# 19V_Converter3_12_2018.net
KiCad netlist of a schematic drawn in Altium Designer
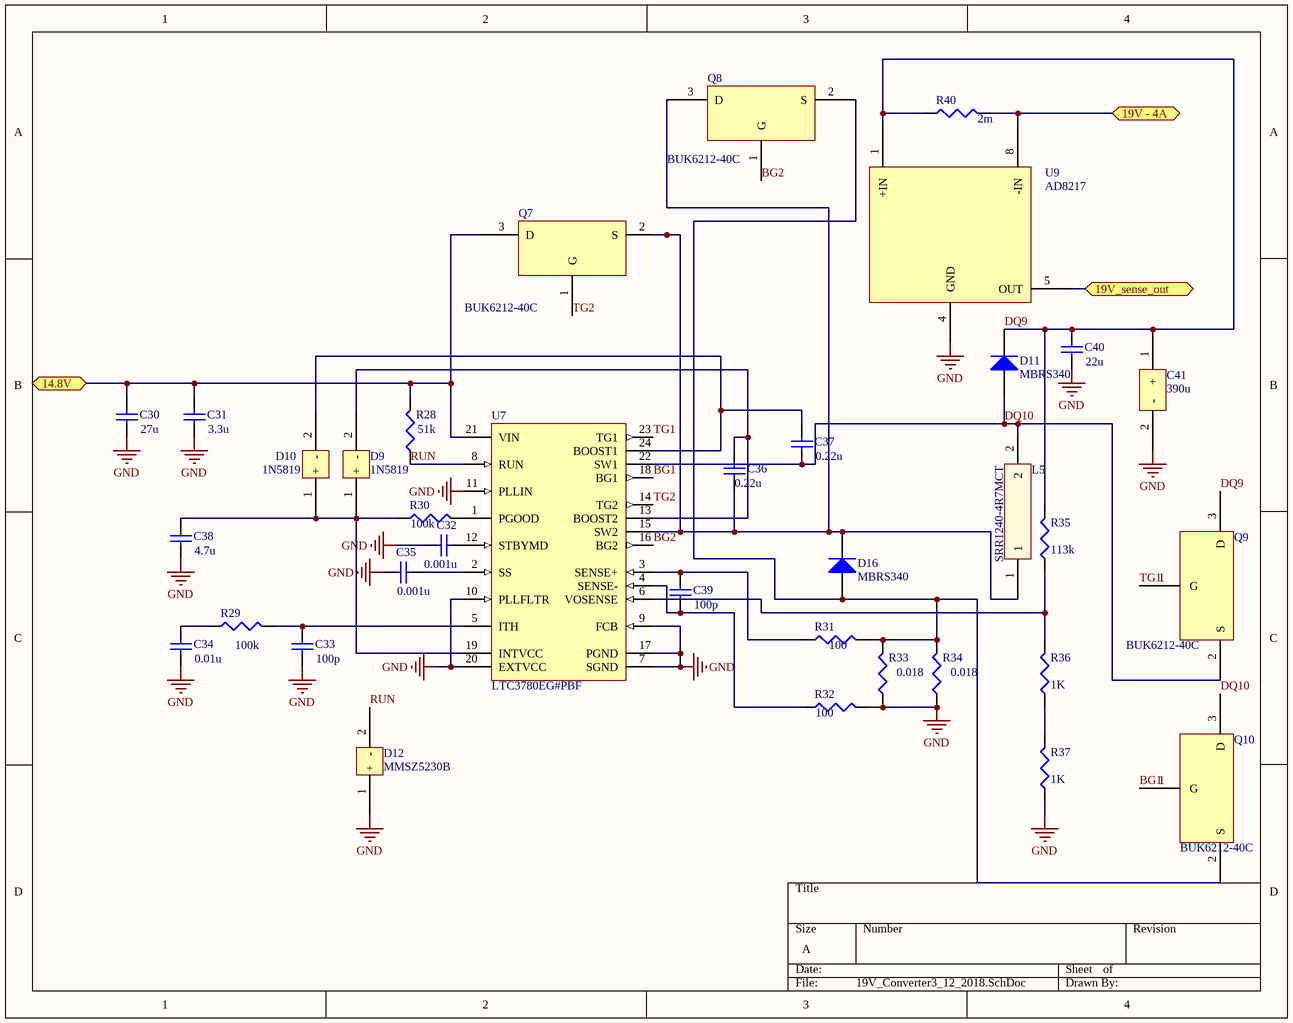
[diagram p0: 19V_Converter3_12_2018.SchDoc]

(export (version "E")
  (design (tool "Eeschema 10.0.6"))
  (components
    (comp (ref "C30")
      (value "27u")
      (footprint "C1206")
      (description "Capacitor (Semiconductor SIM Model)")
      (fields (field (name "Comment") "Cap Semi") (field (name "PUBLISHER") "Altium Limited"))
      (libsource (lib "Miscellaneous Devices") (part "Cap Semi"))
    )
    (comp (ref "C31")
      (value "3.3u")
      (footprint "C1206")
      (description "Capacitor (Semiconductor SIM Model)")
      (fields (field (name "Comment") "Cap Semi") (field (name "PUBLISHER") "Altium Limited"))
      (libsource (lib "Miscellaneous Devices") (part "Cap Semi"))
    )
    (comp (ref "C32")
      (value "0.001u")
      (footprint "C1206")
      (description "Capacitor (Semiconductor SIM Model)")
      (fields (field (name "Comment") "Cap Semi") (field (name "PUBLISHER") "Altium Limited"))
      (libsource (lib "Miscellaneous Devices") (part "Cap Semi"))
    )
    (comp (ref "C33")
      (value "100p")
      (footprint "C1206")
      (description "Capacitor (Semiconductor SIM Model)")
      (fields (field (name "Comment") "Cap Semi") (field (name "PUBLISHER") "Altium Limited"))
      (libsource (lib "Miscellaneous Devices") (part "Cap Semi"))
    )
    (comp (ref "C34")
      (value "0.01u")
      (footprint "C1206")
      (description "Capacitor (Semiconductor SIM Model)")
      (fields (field (name "Comment") "Cap Semi") (field (name "PUBLISHER") "Altium Limited"))
      (libsource (lib "Miscellaneous Devices") (part "Cap Semi"))
    )
    (comp (ref "C35")
      (value "0.001u")
      (footprint "C1206")
      (description "Capacitor (Semiconductor SIM Model)")
      (fields (field (name "Comment") "Cap Semi") (field (name "PUBLISHER") "Altium Limited"))
      (libsource (lib "Miscellaneous Devices") (part "Cap Semi"))
    )
    (comp (ref "C36")
      (value "0.22u")
      (footprint "C1206")
      (description "Capacitor (Semiconductor SIM Model)")
      (fields (field (name "Comment") "Cap Semi") (field (name "PUBLISHER") "Altium Limited"))
      (libsource (lib "Miscellaneous Devices") (part "Cap Semi"))
    )
    (comp (ref "C37")
      (value "0.22u")
      (footprint "C1206")
      (description "Capacitor (Semiconductor SIM Model)")
      (fields (field (name "Comment") "Cap Semi") (field (name "PUBLISHER") "Altium Limited"))
      (libsource (lib "Miscellaneous Devices") (part "Cap Semi"))
    )
    (comp (ref "C38")
      (value "4.7u")
      (footprint "C1206")
      (description "Capacitor (Semiconductor SIM Model)")
      (fields (field (name "Comment") "Cap Semi") (field (name "PUBLISHER") "Altium Limited"))
      (libsource (lib "Miscellaneous Devices") (part "Cap Semi"))
    )
    (comp (ref "C39")
      (value "100p")
      (footprint "C1206")
      (description "Capacitor (Semiconductor SIM Model)")
      (fields (field (name "Comment") "Cap Semi") (field (name "PUBLISHER") "Altium Limited"))
      (libsource (lib "Miscellaneous Devices") (part "Cap Semi"))
    )
    (comp (ref "C40")
      (value "22u")
      (footprint "C1206")
      (description "Capacitor (Semiconductor SIM Model)")
      (fields (field (name "Comment") "Cap Semi") (field (name "PUBLISHER") "Altium Limited"))
      (libsource (lib "Miscellaneous Devices") (part "Cap Semi"))
    )
    (comp (ref "C41")
      (value "390u")
      (footprint "CAPR5-4X5")
      (libsource (lib "AluminumCap") (part "Alum_Cap"))
    )
    (comp (ref "D9")
      (value "1N5819")
      (footprint "SODFL370X175-2N")
      (libsource (lib "Diode (1N5819)") (part "Component_1"))
    )
    (comp (ref "D10")
      (value "1N5819")
      (footprint "SODFL370X175-2N")
      (libsource (lib "Diode (1N5819)") (part "Component_1"))
    )
    (comp (ref "D11")
      (value "MBRS340")
      (footprint "SMC")
      (description "Default Diode")
      (fields (field (name "PUBLISHER") "Altium Limited"))
      (libsource (lib "Miscellaneous Devices") (part "Diode"))
    )
    (comp (ref "D12")
      (value "MMSZ5230B")
      (footprint "SODFL370X175-2N")
      (libsource (lib "Diode (1N5819)") (part "Component_1"))
    )
    (comp (ref "D16")
      (value "MBRS340")
      (footprint "SMC")
      (description "Default Diode")
      (fields (field (name "PUBLISHER") "Altium Limited"))
      (libsource (lib "Miscellaneous Devices") (part "Diode"))
    )
    (comp (ref "L5")
      (value "SRR1240-4R7MCT")
      (footprint "INDP125125X40N")
      (libsource (lib "SRR1240-4R7MCT") (part "SRR1240-4R7MCT"))
    )
    (comp (ref "Q7")
      (value "BUK6212-40C")
      (footprint "DPAK228P1000X238-3N")
      (libsource (lib "BUK6212-40C") (part "Component_1"))
    )
    (comp (ref "Q8")
      (value "BUK6212-40C")
      (footprint "DPAK228P1000X238-3N")
      (libsource (lib "BUK6212-40C") (part "Component_1"))
    )
    (comp (ref "Q9")
      (value "BUK6212-40C")
      (footprint "DPAK228P1000X238-3N")
      (libsource (lib "") (part "Component_1_1"))
    )
    (comp (ref "Q10")
      (value "BUK6212-40C")
      (footprint "DPAK228P1000X238-3N")
      (libsource (lib "") (part "Component_1_1"))
    )
    (comp (ref "R28")
      (value "51k")
      (footprint "J1-0603")
      (description "Resistor")
      (fields (field (name "Comment") "Res3") (field (name "PUBLISHER") "Altium Limited"))
      (libsource (lib "Miscellaneous Devices") (part "Res3"))
    )
    (comp (ref "R29")
      (value "100k")
      (footprint "J1-0603")
      (description "Resistor")
      (fields (field (name "Comment") "Res3") (field (name "PUBLISHER") "Altium Limited"))
      (libsource (lib "Miscellaneous Devices") (part "Res3"))
    )
    (comp (ref "R30")
      (value "100k")
      (footprint "J1-0603")
      (description "Resistor")
      (fields (field (name "Comment") "Res3") (field (name "PUBLISHER") "Altium Limited"))
      (libsource (lib "Miscellaneous Devices") (part "Res3"))
    )
    (comp (ref "R31")
      (value "100")
      (footprint "J1-0603")
      (description "Resistor")
      (fields (field (name "Comment") "Res3") (field (name "PUBLISHER") "Altium Limited"))
      (libsource (lib "Miscellaneous Devices") (part "Res3"))
    )
    (comp (ref "R32")
      (value "100")
      (footprint "J1-0603")
      (description "Resistor")
      (fields (field (name "Comment") "Res3") (field (name "PUBLISHER") "Altium Limited"))
      (libsource (lib "Miscellaneous Devices") (part "Res3"))
    )
    (comp (ref "R33")
      (value "0.018")
      (footprint "J1-0603")
      (description "Resistor")
      (fields (field (name "Comment") "Res3") (field (name "PUBLISHER") "Altium Limited"))
      (libsource (lib "Miscellaneous Devices") (part "Res3"))
    )
    (comp (ref "R34")
      (value "0.018")
      (footprint "J1-0603")
      (description "Resistor")
      (fields (field (name "Comment") "Res3") (field (name "PUBLISHER") "Altium Limited"))
      (libsource (lib "Miscellaneous Devices") (part "Res3"))
    )
    (comp (ref "R35")
      (value "113k")
      (footprint "J1-0603")
      (description "Resistor")
      (fields (field (name "Comment") "Res3") (field (name "PUBLISHER") "Altium Limited"))
      (libsource (lib "Miscellaneous Devices") (part "Res3"))
    )
    (comp (ref "R36")
      (value "1K")
      (footprint "J1-0603")
      (description "Resistor")
      (fields (field (name "Comment") "Res3") (field (name "PUBLISHER") "Altium Limited"))
      (libsource (lib "Miscellaneous Devices") (part "Res3"))
    )
    (comp (ref "R37")
      (value "1K")
      (footprint "J1-0603")
      (description "Resistor")
      (fields (field (name "Comment") "Res3") (field (name "PUBLISHER") "Altium Limited"))
      (libsource (lib "Miscellaneous Devices") (part "Res3"))
    )
    (comp (ref "R40")
      (value "2m")
      (footprint "14-1210")
      (description "Resistor")
      (fields (field (name "Comment") "Res3") (field (name "PUBLISHER") "Altium Limited"))
      (libsource (lib "Miscellaneous Devices") (part "Res3"))
    )
    (comp (ref "U7")
      (value "LTC3780EG#PBF")
      (footprint "SOP65P780X200-24N")
      (fields (field (name "MANUFACTURER") "Linear Technology"))
      (libsource (lib "Linear Technology Power Management Switching Regulator LTC1174-LTC3901") (part "LTC3780EG#PBF"))
    )
    (comp (ref "U9")
      (value "AD8217")
      (footprint "TSOP65P490X110-8N")
      (description "Current Shunt Moniter")
      (libsource (lib "AD8217") (part "Component_1"))
    )
  )
  (nets
    (net (code "1") (name "/14.8V") (class "Default")
      (node (ref "C30") (pin "2") (pinfunction "2_2") (pintype "passive"))
      (node (ref "C31") (pin "2") (pinfunction "2_2") (pintype "passive"))
      (node (ref "Q7") (pin "3") (pinfunction "D_3") (pintype "passive"))
      (node (ref "R28") (pin "2") (pinfunction "2_2") (pintype "passive"))
      (node (ref "U7") (pin "21") (pinfunction "VIN_21") (pintype "power_in"))
    )
    (net (code "2") (name "/19V - 4A") (class "Default")
      (node (ref "R40") (pin "2") (pinfunction "2_2") (pintype "passive"))
      (node (ref "U9") (pin "8") (pinfunction "-IN_8") (pintype "passive"))
    )
    (net (code "3") (name "/19V_sense_out") (class "Default")
      (node (ref "U9") (pin "5") (pinfunction "OUT_5") (pintype "passive"))
    )
    (net (code "4") (name "/BG1") (class "Default")
      (node (ref "Q10") (pin "1") (pinfunction "G_1") (pintype "passive"))
      (node (ref "U7") (pin "18") (pinfunction "BG1_18") (pintype "output"))
    )
    (net (code "5") (name "/BG2") (class "Default")
      (node (ref "Q8") (pin "1") (pinfunction "G_1") (pintype "passive"))
      (node (ref "U7") (pin "16") (pinfunction "BG2_16") (pintype "output"))
    )
    (net (code "6") (name "/DQ9") (class "Default")
      (node (ref "C40") (pin "2") (pinfunction "2_2") (pintype "passive"))
      (node (ref "C41") (pin "1") (pinfunction "+_1") (pintype "passive"))
      (node (ref "D11") (pin "2") (pinfunction "K_2") (pintype "passive"))
      (node (ref "Q9") (pin "3") (pinfunction "D_3") (pintype "passive"))
      (node (ref "R35") (pin "2") (pinfunction "2_2") (pintype "passive"))
      (node (ref "R40") (pin "1") (pinfunction "1_1") (pintype "passive"))
      (node (ref "U9") (pin "1") (pinfunction "+IN_1") (pintype "passive"))
    )
    (net (code "7") (name "/DQ10") (class "Default")
      (node (ref "C37") (pin "1") (pinfunction "1_1") (pintype "passive"))
      (node (ref "D11") (pin "1") (pinfunction "A_1") (pintype "passive"))
      (node (ref "L5") (pin "2") (pinfunction "2_2") (pintype "passive"))
      (node (ref "Q10") (pin "3") (pinfunction "D_3") (pintype "passive"))
      (node (ref "Q9") (pin "2") (pinfunction "S_2") (pintype "passive"))
      (node (ref "U7") (pin "22") (pinfunction "SW1_22") (pintype "passive"))
    )
    (net (code "8") (name "/RUN") (class "Default")
      (node (ref "D12") (pin "2") (pinfunction "-_2") (pintype "passive"))
      (node (ref "R28") (pin "1") (pinfunction "1_1") (pintype "passive"))
      (node (ref "U7") (pin "8") (pinfunction "RUN_8") (pintype "input"))
    )
    (net (code "9") (name "/TG1") (class "Default")
      (node (ref "Q9") (pin "1") (pinfunction "G_1") (pintype "passive"))
      (node (ref "U7") (pin "23") (pinfunction "TG1_23") (pintype "output"))
    )
    (net (code "10") (name "/TG2") (class "Default")
      (node (ref "Q7") (pin "1") (pinfunction "G_1") (pintype "passive"))
      (node (ref "U7") (pin "14") (pinfunction "TG2_14") (pintype "output"))
    )
    (net (code "11") (name "GND") (class "Default")
      (node (ref "C30") (pin "1") (pinfunction "1_1") (pintype "passive"))
      (node (ref "C31") (pin "1") (pinfunction "1_1") (pintype "passive"))
      (node (ref "C32") (pin "1") (pinfunction "1_1") (pintype "passive"))
      (node (ref "C33") (pin "1") (pinfunction "1_1") (pintype "passive"))
      (node (ref "C34") (pin "1") (pinfunction "1_1") (pintype "passive"))
      (node (ref "C35") (pin "1") (pinfunction "1_1") (pintype "passive"))
      (node (ref "C38") (pin "1") (pinfunction "1_1") (pintype "passive"))
      (node (ref "C40") (pin "1") (pinfunction "1_1") (pintype "passive"))
      (node (ref "C41") (pin "2") (pinfunction "-_2") (pintype "passive"))
      (node (ref "D12") (pin "1") (pinfunction "+_1") (pintype "passive"))
      (node (ref "R32") (pin "2") (pinfunction "2_2") (pintype "passive"))
      (node (ref "R33") (pin "1") (pinfunction "1_1") (pintype "passive"))
      (node (ref "R34") (pin "1") (pinfunction "1_1") (pintype "passive"))
      (node (ref "R37") (pin "1") (pinfunction "1_1") (pintype "passive"))
      (node (ref "U7") (pin "10") (pinfunction "PLLFLTR_10") (pintype "input"))
      (node (ref "U7") (pin "11") (pinfunction "PLLIN_11") (pintype "input"))
      (node (ref "U7") (pin "17") (pinfunction "PGND_17") (pintype "power_in"))
      (node (ref "U7") (pin "20") (pinfunction "EXTVCC_20") (pintype "power_in"))
      (node (ref "U7") (pin "7") (pinfunction "SGND_7") (pintype "power_in"))
      (node (ref "U7") (pin "9") (pinfunction "FCB_9") (pintype "input"))
      (node (ref "U9") (pin "4") (pinfunction "GND_4") (pintype "passive"))
    )
    (net (code "12") (name "Net-(C34-Pad2)") (class "Default")
      (node (ref "C34") (pin "2") (pinfunction "2_2") (pintype "passive"))
      (node (ref "R29") (pin "1") (pinfunction "1_1") (pintype "passive"))
    )
    (net (code "13") (name "Net-(D9--)") (class "Default")
      (node (ref "C36") (pin "2") (pinfunction "2_2") (pintype "passive"))
      (node (ref "D9") (pin "2") (pinfunction "-_2") (pintype "passive"))
      (node (ref "U7") (pin "13") (pinfunction "BOOST2_13") (pintype "passive"))
    )
    (net (code "14") (name "Net-(D10-+)") (class "Default")
      (node (ref "C38") (pin "2") (pinfunction "2_2") (pintype "passive"))
      (node (ref "D10") (pin "1") (pinfunction "+_1") (pintype "passive"))
      (node (ref "D9") (pin "1") (pinfunction "+_1") (pintype "passive"))
      (node (ref "R30") (pin "1") (pinfunction "1_1") (pintype "passive"))
      (node (ref "U7") (pin "19") (pinfunction "INTVCC_19") (pintype "power_in"))
    )
    (net (code "15") (name "Net-(D10--)") (class "Default")
      (node (ref "C37") (pin "2") (pinfunction "2_2") (pintype "passive"))
      (node (ref "D10") (pin "2") (pinfunction "-_2") (pintype "passive"))
      (node (ref "U7") (pin "24") (pinfunction "BOOST1_24") (pintype "passive"))
    )
    (net (code "16") (name "Net-(D16-A)") (class "Default")
      (node (ref "D16") (pin "1") (pinfunction "A_1") (pintype "passive"))
      (node (ref "Q10") (pin "2") (pinfunction "S_2") (pintype "passive"))
      (node (ref "Q8") (pin "2") (pinfunction "S_2") (pintype "passive"))
      (node (ref "R31") (pin "2") (pinfunction "2_2") (pintype "passive"))
      (node (ref "R33") (pin "2") (pinfunction "2_2") (pintype "passive"))
      (node (ref "R34") (pin "2") (pinfunction "2_2") (pintype "passive"))
    )
    (net (code "17") (name "Net-(D16-K)") (class "Default")
      (node (ref "C36") (pin "1") (pinfunction "1_1") (pintype "passive"))
      (node (ref "D16") (pin "2") (pinfunction "K_2") (pintype "passive"))
      (node (ref "L5") (pin "1") (pinfunction "1_1") (pintype "passive"))
      (node (ref "Q7") (pin "2") (pinfunction "S_2") (pintype "passive"))
      (node (ref "Q8") (pin "3") (pinfunction "D_3") (pintype "passive"))
      (node (ref "U7") (pin "15") (pinfunction "SW2_15") (pintype "passive"))
    )
    (net (code "18") (name "Net-(R36-Pad1)") (class "Default")
      (node (ref "R36") (pin "1") (pinfunction "1_1") (pintype "passive"))
      (node (ref "R37") (pin "2") (pinfunction "2_2") (pintype "passive"))
    )
    (net (code "19") (name "Net-(U7-ITH)") (class "Default")
      (node (ref "C33") (pin "2") (pinfunction "2_2") (pintype "passive"))
      (node (ref "R29") (pin "2") (pinfunction "2_2") (pintype "passive"))
      (node (ref "U7") (pin "5") (pinfunction "ITH_5") (pintype "passive"))
    )
    (net (code "20") (name "Net-(U7-PGOOD)") (class "Default")
      (node (ref "R30") (pin "2") (pinfunction "2_2") (pintype "passive"))
      (node (ref "U7") (pin "1") (pinfunction "PGOOD_1") (pintype "open_collector"))
    )
    (net (code "21") (name "Net-(U7-SENSE+)") (class "Default")
      (node (ref "C39") (pin "2") (pinfunction "2_2") (pintype "passive"))
      (node (ref "R31") (pin "1") (pinfunction "1_1") (pintype "passive"))
      (node (ref "U7") (pin "3") (pinfunction "SENSE+_3") (pintype "input"))
    )
    (net (code "22") (name "Net-(U7-SENSE-)") (class "Default")
      (node (ref "C39") (pin "1") (pinfunction "1_1") (pintype "passive"))
      (node (ref "R32") (pin "1") (pinfunction "1_1") (pintype "passive"))
      (node (ref "U7") (pin "4") (pinfunction "SENSE-_4") (pintype "input"))
    )
    (net (code "23") (name "Net-(U7-SS)") (class "Default")
      (node (ref "C35") (pin "2") (pinfunction "2_2") (pintype "passive"))
      (node (ref "U7") (pin "2") (pinfunction "SS_2") (pintype "input"))
    )
    (net (code "24") (name "Net-(U7-STBYMD)") (class "Default")
      (node (ref "C32") (pin "2") (pinfunction "2_2") (pintype "passive"))
      (node (ref "U7") (pin "12") (pinfunction "STBYMD_12") (pintype "input"))
    )
    (net (code "25") (name "Net-(U7-VOSENSE)") (class "Default")
      (node (ref "R35") (pin "1") (pinfunction "1_1") (pintype "passive"))
      (node (ref "R36") (pin "2") (pinfunction "2_2") (pintype "passive"))
      (node (ref "U7") (pin "6") (pinfunction "VOSENSE_6") (pintype "input"))
    )
  )
)
